# ESP32.net
KiCad netlist of a schematic drawn in Altium Designer
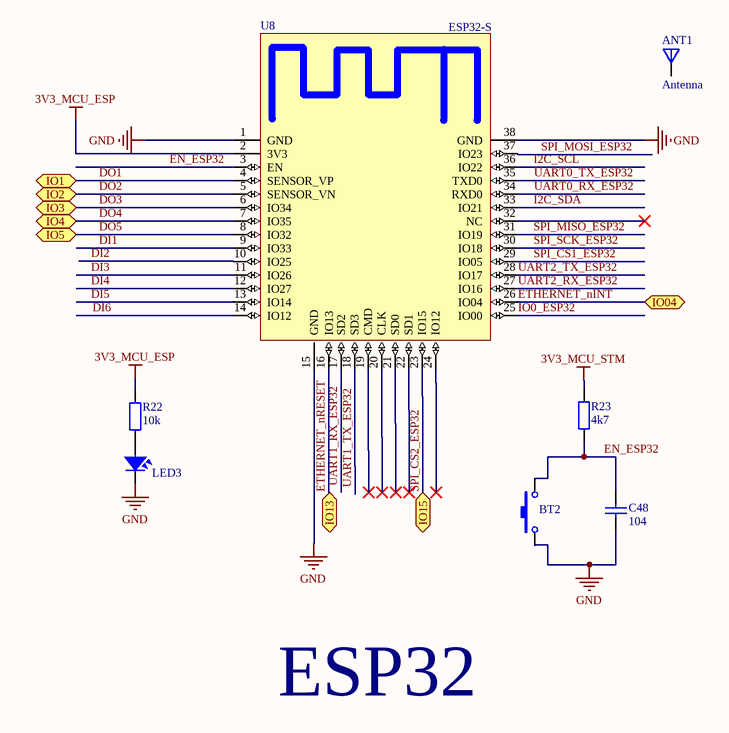
[diagram p0: ESP32.SchDoc]

(export (version "E")
  (design (tool "Eeschema 10.0.6"))
  (components
    (comp (ref "ANT1") (value "Antenna") (footprint "ANTENNA") (libsource (lib "CMN") (part "Antenna")))
    (comp (ref "BT2")
      (value "SW")
      (footprint "BUTTON RIGHT ANGLE")
      (description "Switch-Button")
      (fields (field (name "PUBLISHER") "Altium Limited"))
      (libsource (lib "KhanhBK_Library_4") (part "SW-Button"))
    )
    (comp (ref "C48") (value "104") (footprint "0603_Cap") (libsource (lib "CMN") (part "Ceramic Capacitor")))
    (comp (ref "LED3")
      (value "LED")
      (footprint "0603_LED")
      (description "LED single color 2 leads")
      (libsource (lib "CMN") (part "LED"))
    )
    (comp (ref "R22") (value "10k") (footprint "0603_Res") (libsource (lib "CMN") (part "Resistor")))
    (comp (ref "R23") (value "4k7") (footprint "0603_Res") (libsource (lib "CMN") (part "Resistor")))
    (comp (ref "U8") (value "ESP32-S") (footprint "ESP32-S") (libsource (lib "CMN") (part "ESP32-S")))
  )
  (nets
    (net (code "1") (name "/DI1") (class "Default")
      (node (ref "U8") (pin "9") (pinfunction "IO33_9") (pintype "bidirectional"))
    )
    (net (code "2") (name "/DI2") (class "Default")
      (node (ref "U8") (pin "10") (pinfunction "IO25_10") (pintype "bidirectional"))
    )
    (net (code "3") (name "/DI3") (class "Default")
      (node (ref "U8") (pin "11") (pinfunction "IO26_11") (pintype "bidirectional"))
    )
    (net (code "4") (name "/DI4") (class "Default")
      (node (ref "U8") (pin "12") (pinfunction "IO27_12") (pintype "bidirectional"))
    )
    (net (code "5") (name "/DI5") (class "Default")
      (node (ref "U8") (pin "13") (pinfunction "IO14_13") (pintype "bidirectional"))
    )
    (net (code "6") (name "/DI6") (class "Default")
      (node (ref "U8") (pin "14") (pinfunction "IO12_14") (pintype "bidirectional"))
    )
    (net (code "7") (name "/DO1") (class "Default")
      (node (ref "U8") (pin "4") (pinfunction "SENSOR_VP_4") (pintype "bidirectional"))
    )
    (net (code "8") (name "/DO2") (class "Default")
      (node (ref "U8") (pin "5") (pinfunction "SENSOR_VN_5") (pintype "bidirectional"))
    )
    (net (code "9") (name "/DO3") (class "Default")
      (node (ref "U8") (pin "6") (pinfunction "IO34_6") (pintype "bidirectional"))
    )
    (net (code "10") (name "/DO4") (class "Default")
      (node (ref "U8") (pin "7") (pinfunction "IO35_7") (pintype "bidirectional"))
    )
    (net (code "11") (name "/DO5") (class "Default")
      (node (ref "U8") (pin "8") (pinfunction "IO32_8") (pintype "bidirectional"))
    )
    (net (code "12") (name "/EN_ESP32") (class "Default")
      (node (ref "BT2") (pin "2") (pinfunction "2_2") (pintype "passive"))
      (node (ref "C48") (pin "2") (pinfunction "2_2") (pintype "passive"))
      (node (ref "R23") (pin "1") (pinfunction "1_1") (pintype "passive"))
      (node (ref "U8") (pin "3") (pinfunction "EN_3") (pintype "bidirectional"))
    )
    (net (code "13") (name "/ETHERNET_nINT") (class "Default")
      (node (ref "U8") (pin "26") (pinfunction "IO04_26") (pintype "bidirectional"))
    )
    (net (code "14") (name "/ETHERNET_nRESET") (class "Default")
      (node (ref "U8") (pin "16") (pinfunction "IO13_16") (pintype "bidirectional"))
    )
    (net (code "15") (name "/I2C_SCL") (class "Default")
      (node (ref "U8") (pin "36") (pinfunction "IO22_36") (pintype "bidirectional"))
    )
    (net (code "16") (name "/I2C_SDA") (class "Default")
      (node (ref "U8") (pin "33") (pinfunction "IO21_33") (pintype "bidirectional"))
    )
    (net (code "17") (name "/IO0_ESP32") (class "Default")
      (node (ref "U8") (pin "25") (pinfunction "IO00_25") (pintype "bidirectional"))
    )
    (net (code "18") (name "/SPI_CS1_ESP32") (class "Default")
      (node (ref "U8") (pin "29") (pinfunction "IO05_29") (pintype "bidirectional"))
    )
    (net (code "19") (name "/SPI_CS2_ESP32") (class "Default")
      (node (ref "U8") (pin "23") (pinfunction "IO15_23") (pintype "bidirectional"))
    )
    (net (code "20") (name "/SPI_MISO_ESP32") (class "Default")
      (node (ref "U8") (pin "31") (pinfunction "IO19_31") (pintype "bidirectional"))
    )
    (net (code "21") (name "/SPI_MOSI_ESP32") (class "Default")
      (node (ref "U8") (pin "37") (pinfunction "IO23_37") (pintype "bidirectional"))
    )
    (net (code "22") (name "/SPI_SCK_ESP32") (class "Default")
      (node (ref "U8") (pin "30") (pinfunction "IO18_30") (pintype "bidirectional"))
    )
    (net (code "23") (name "/UART0_RX_ESP32") (class "Default")
      (node (ref "U8") (pin "34") (pinfunction "RXD0_34") (pintype "bidirectional"))
    )
    (net (code "24") (name "/UART0_TX_ESP32") (class "Default")
      (node (ref "U8") (pin "35") (pinfunction "TXD0_35") (pintype "bidirectional"))
    )
    (net (code "25") (name "/UART1_RX_ESP32") (class "Default")
      (node (ref "U8") (pin "17") (pinfunction "SD2_17") (pintype "bidirectional"))
    )
    (net (code "26") (name "/UART1_TX_ESP32") (class "Default")
      (node (ref "U8") (pin "18") (pinfunction "SD3_18") (pintype "bidirectional"))
    )
    (net (code "27") (name "/UART2_RX_ESP32") (class "Default")
      (node (ref "U8") (pin "27") (pinfunction "IO16_27") (pintype "bidirectional"))
    )
    (net (code "28") (name "/UART2_TX_ESP32") (class "Default")
      (node (ref "U8") (pin "28") (pinfunction "IO17_28") (pintype "bidirectional"))
    )
    (net (code "29") (name "3V3_MCU_ESP") (class "Default")
      (node (ref "R22") (pin "2") (pinfunction "2_2") (pintype "passive"))
      (node (ref "U8") (pin "2") (pinfunction "3V3_2") (pintype "power_in"))
    )
    (net (code "30") (name "3V3_MCU_STM") (class "Default")
      (node (ref "R23") (pin "2") (pinfunction "2_2") (pintype "passive"))
    )
    (net (code "31") (name "GND") (class "Default")
      (node (ref "BT2") (pin "1") (pinfunction "1_1") (pintype "passive"))
      (node (ref "C48") (pin "1") (pinfunction "1_1") (pintype "passive"))
      (node (ref "LED3") (pin "C") (pinfunction "Cathode_C") (pintype "passive"))
      (node (ref "U8") (pin "1") (pinfunction "GND_1") (pintype "power_in"))
      (node (ref "U8") (pin "15") (pinfunction "GND_15") (pintype "power_in"))
      (node (ref "U8") (pin "38") (pinfunction "GND_38") (pintype "power_in"))
    )
    (net (code "32") (name "Net-(LED3-Anode)") (class "Default")
      (node (ref "LED3") (pin "A") (pinfunction "Anode_A") (pintype "passive"))
      (node (ref "R22") (pin "1") (pinfunction "1_1") (pintype "passive"))
    )
    (net (code "33") (name "unconnected-(ANT1-ANT-Pad1)") (class "Default")
      (node (ref "ANT1") (pin "1") (pinfunction "ANT_1") (pintype "passive"))
    )
    (net (code "34") (name "unconnected-(U8-CLK-Pad20)") (class "Default")
      (node (ref "U8") (pin "20") (pinfunction "CLK_20") (pintype "bidirectional+no_connect"))
    )
    (net (code "35") (name "unconnected-(U8-CMD-Pad19)") (class "Default")
      (node (ref "U8") (pin "19") (pinfunction "CMD_19") (pintype "bidirectional+no_connect"))
    )
    (net (code "36") (name "unconnected-(U8-IO12-Pad24)") (class "Default")
      (node (ref "U8") (pin "24") (pinfunction "IO12_24") (pintype "bidirectional+no_connect"))
    )
    (net (code "37") (name "unconnected-(U8-NC-Pad32)") (class "Default")
      (node (ref "U8") (pin "32") (pinfunction "NC_32") (pintype "bidirectional+no_connect"))
    )
    (net (code "38") (name "unconnected-(U8-SD0-Pad21)") (class "Default")
      (node (ref "U8") (pin "21") (pinfunction "SD0_21") (pintype "bidirectional+no_connect"))
    )
    (net (code "39") (name "unconnected-(U8-SD1-Pad22)") (class "Default")
      (node (ref "U8") (pin "22") (pinfunction "SD1_22") (pintype "bidirectional+no_connect"))
    )
  )
)
